# CAN.net
KiCad netlist of a schematic drawn in Altium Designer
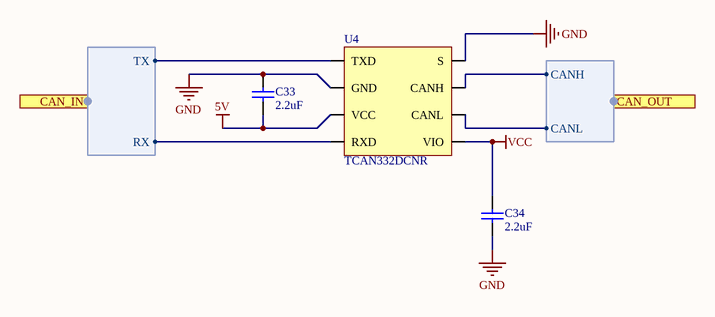
[diagram p0: CAN.SchDoc]

(export (version "E")
  (design (tool "Eeschema 10.0.6"))
  (components
    (comp (ref "C33")
      (value "2.2uF")
      (footprint "C0603[1608X92]")
      (description "2.2uF 6.3V 10% 0603 (1608 Metric)")
      (fields (field (name "PARTNUMBER") "GRM185R60J225KE26D") (field (name "MANUFACTURER") "Murata"))
      (libsource (lib "Capacitors") (part "CAP_2.2uF_6.3V_0603_10%"))
    )
    (comp (ref "C34")
      (value "2.2uF")
      (footprint "C0603[1608X92]")
      (description "2.2uF 6.3V 10% 0603 (1608 Metric)")
      (fields (field (name "PARTNUMBER") "GRM185R60J225KE26D") (field (name "MANUFACTURER") "Murata"))
      (libsource (lib "Capacitors") (part "CAP_2.2uF_6.3V_0603_10%"))
    )
    (comp (ref "U4")
      (value "TCAN332DCNR")
      (footprint "SOT-23-8")
      (description "CAN Interface IC 5V CAN Transceivers 8-SOT-23 -40 to 150")
      (fields (field (name "MANUFACTURER") "NXP Semiconductors") (field (name "PARTNUMBER") "TJA1051T/3"))
      (libsource (lib "ICs") (part "TJA1051T/3"))
    )
  )
  (nets
    (net (code "4") (name "/CANH") (class "Default")
      (node (ref "U4") (pin "7") (pinfunction "CANH_7") (pintype "passive"))
    )
    (net (code "5") (name "/CANL") (class "Default")
      (node (ref "U4") (pin "6") (pinfunction "CANL_6") (pintype "passive"))
    )
    (net (code "6") (name "/RX") (class "Default")
      (node (ref "U4") (pin "4") (pinfunction "RXD_4") (pintype "passive"))
    )
    (net (code "7") (name "/TX") (class "Default")
      (node (ref "U4") (pin "1") (pinfunction "TXD_1") (pintype "passive"))
    )
    (net (code "10") (name "5V") (class "Default")
      (node (ref "C33") (pin "1") (pinfunction "1_1") (pintype "passive"))
      (node (ref "U4") (pin "3") (pinfunction "VCC_3") (pintype "passive"))
    )
    (net (code "11") (name "GND") (class "Default")
      (node (ref "C33") (pin "2") (pinfunction "2_2") (pintype "passive"))
      (node (ref "C34") (pin "1") (pinfunction "1_1") (pintype "passive"))
      (node (ref "U4") (pin "2") (pinfunction "GND_2") (pintype "passive"))
      (node (ref "U4") (pin "8") (pinfunction "S_8") (pintype "passive"))
    )
    (net (code "12") (name "VCC") (class "Default")
      (node (ref "C34") (pin "2") (pinfunction "2_2") (pintype "passive"))
      (node (ref "U4") (pin "5") (pinfunction "VIO_5") (pintype "passive"))
    )
  )
)
